# LPDDR4X_Power.net
KiCad netlist of a schematic drawn in Altium Designer
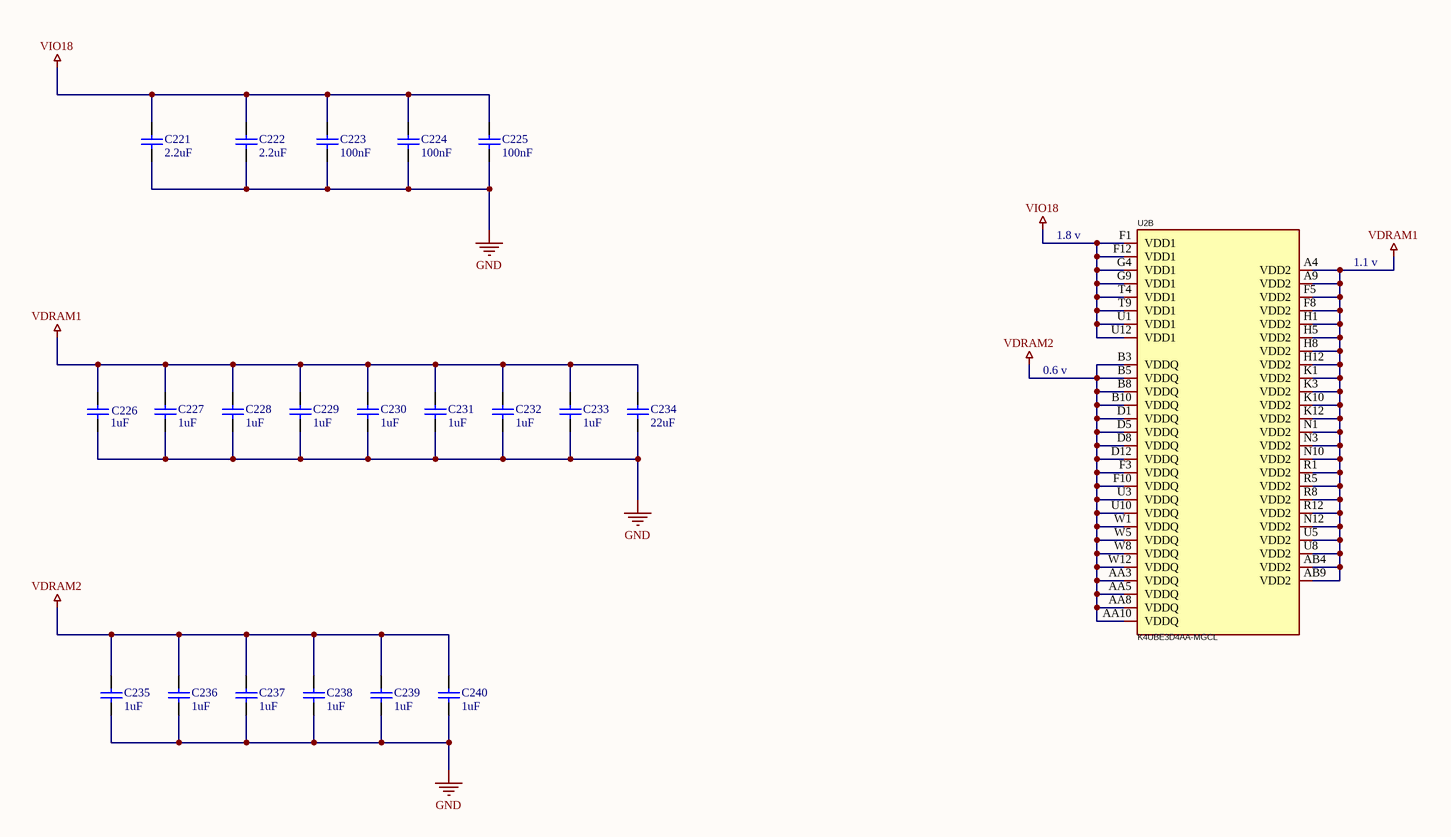
[diagram p0: LPDDR4X_Power.SchDoc]

(export (version "E")
  (design (tool "Eeschema 10.0.6"))
  (components
    (comp (ref "C221")
      (value "2.2uF")
      (footprint "C0805")
      (fields (field (name "Comment") "C0805"))
      (libsource (lib "kit") (part "C0805"))
    )
    (comp (ref "C222")
      (value "2.2uF")
      (footprint "C0805")
      (fields (field (name "Comment") "C0805"))
      (libsource (lib "kit") (part "C0805"))
    )
    (comp (ref "C223")
      (value "100nF")
      (footprint "C0603")
      (fields (field (name "Comment") "C0603"))
      (libsource (lib "kit") (part "C0603"))
    )
    (comp (ref "C224")
      (value "100nF")
      (footprint "C0603")
      (fields (field (name "Comment") "C0603"))
      (libsource (lib "kit") (part "C0603"))
    )
    (comp (ref "C225")
      (value "100nF")
      (footprint "C0603")
      (fields (field (name "Comment") "C0603"))
      (libsource (lib "kit") (part "C0603"))
    )
    (comp (ref "C226")
      (value "1uF")
      (footprint "C0805")
      (fields (field (name "Comment") "C0805"))
      (libsource (lib "kit") (part "C0805"))
    )
    (comp (ref "C227")
      (value "1uF")
      (footprint "C0805")
      (fields (field (name "Comment") "C0805"))
      (libsource (lib "kit") (part "C0805"))
    )
    (comp (ref "C228")
      (value "1uF")
      (footprint "C0805")
      (fields (field (name "Comment") "C0805"))
      (libsource (lib "kit") (part "C0805"))
    )
    (comp (ref "C229")
      (value "1uF")
      (footprint "C0805")
      (fields (field (name "Comment") "C0805"))
      (libsource (lib "kit") (part "C0805"))
    )
    (comp (ref "C230")
      (value "1uF")
      (footprint "C0805")
      (fields (field (name "Comment") "C0805"))
      (libsource (lib "kit") (part "C0805"))
    )
    (comp (ref "C231")
      (value "1uF")
      (footprint "C0805")
      (fields (field (name "Comment") "C0805"))
      (libsource (lib "kit") (part "C0805"))
    )
    (comp (ref "C232")
      (value "1uF")
      (footprint "C0805")
      (fields (field (name "Comment") "C0805"))
      (libsource (lib "kit") (part "C0805"))
    )
    (comp (ref "C233")
      (value "1uF")
      (footprint "C0805")
      (fields (field (name "Comment") "C0805"))
      (libsource (lib "kit") (part "C0805"))
    )
    (comp (ref "C234")
      (value "22uF")
      (footprint "C1210")
      (fields (field (name "Comment") "C1210"))
      (libsource (lib "kit") (part "C1210"))
    )
    (comp (ref "C235")
      (value "1uF")
      (footprint "C0805")
      (fields (field (name "Comment") "C0805"))
      (libsource (lib "kit") (part "C0805"))
    )
    (comp (ref "C236")
      (value "1uF")
      (footprint "C0805")
      (fields (field (name "Comment") "C0805"))
      (libsource (lib "kit") (part "C0805"))
    )
    (comp (ref "C237")
      (value "1uF")
      (footprint "C0805")
      (fields (field (name "Comment") "C0805"))
      (libsource (lib "kit") (part "C0805"))
    )
    (comp (ref "C238")
      (value "1uF")
      (footprint "C0805")
      (fields (field (name "Comment") "C0805"))
      (libsource (lib "kit") (part "C0805"))
    )
    (comp (ref "C239")
      (value "1uF")
      (footprint "C0805")
      (fields (field (name "Comment") "C0805"))
      (libsource (lib "kit") (part "C0805"))
    )
    (comp (ref "C240")
      (value "1uF")
      (footprint "C0805")
      (fields (field (name "Comment") "C0805"))
      (libsource (lib "kit") (part "C0805"))
    )
    (comp (ref "U2")
      (value "K4UBE3D4AA-MGCL")
      (footprint "K4F8E304HB-MGCJ")
      (fields (field (name "MANUFACTURER") "SAMSUNG(三星半导体)"))
      (libsource (lib "kit") (part "K4UBE3D4AA-MGCL"))
    )
  )
  (nets
    (net (code "1") (name "GND") (class "Default")
      (node (ref "C221") (pin "1") (pinfunction "1_1") (pintype "passive"))
      (node (ref "C222") (pin "1") (pinfunction "1_1") (pintype "passive"))
      (node (ref "C223") (pin "1") (pinfunction "1_1") (pintype "passive"))
      (node (ref "C224") (pin "1") (pinfunction "1_1") (pintype "passive"))
      (node (ref "C225") (pin "1") (pinfunction "1_1") (pintype "passive"))
      (node (ref "C226") (pin "1") (pinfunction "1_1") (pintype "passive"))
      (node (ref "C227") (pin "1") (pinfunction "1_1") (pintype "passive"))
      (node (ref "C228") (pin "1") (pinfunction "1_1") (pintype "passive"))
      (node (ref "C229") (pin "1") (pinfunction "1_1") (pintype "passive"))
      (node (ref "C230") (pin "1") (pinfunction "1_1") (pintype "passive"))
      (node (ref "C231") (pin "1") (pinfunction "1_1") (pintype "passive"))
      (node (ref "C232") (pin "1") (pinfunction "1_1") (pintype "passive"))
      (node (ref "C233") (pin "1") (pinfunction "1_1") (pintype "passive"))
      (node (ref "C234") (pin "1") (pinfunction "1_1") (pintype "passive"))
      (node (ref "C235") (pin "1") (pinfunction "1_1") (pintype "passive"))
      (node (ref "C236") (pin "1") (pinfunction "1_1") (pintype "passive"))
      (node (ref "C237") (pin "1") (pinfunction "1_1") (pintype "passive"))
      (node (ref "C238") (pin "1") (pinfunction "1_1") (pintype "passive"))
      (node (ref "C239") (pin "1") (pinfunction "1_1") (pintype "passive"))
      (node (ref "C240") (pin "1") (pinfunction "1_1") (pintype "passive"))
    )
    (net (code "2") (name "VDRAM1") (class "Default")
      (node (ref "C226") (pin "2") (pinfunction "2_2") (pintype "passive"))
      (node (ref "C227") (pin "2") (pinfunction "2_2") (pintype "passive"))
      (node (ref "C228") (pin "2") (pinfunction "2_2") (pintype "passive"))
      (node (ref "C229") (pin "2") (pinfunction "2_2") (pintype "passive"))
      (node (ref "C230") (pin "2") (pinfunction "2_2") (pintype "passive"))
      (node (ref "C231") (pin "2") (pinfunction "2_2") (pintype "passive"))
      (node (ref "C232") (pin "2") (pinfunction "2_2") (pintype "passive"))
      (node (ref "C233") (pin "2") (pinfunction "2_2") (pintype "passive"))
      (node (ref "C234") (pin "2") (pinfunction "2_2") (pintype "passive"))
      (node (ref "U2") (pin "A4") (pinfunction "VDD2_A4") (pintype "passive"))
      (node (ref "U2") (pin "A9") (pinfunction "VDD2_A9") (pintype "passive"))
      (node (ref "U2") (pin "AB4") (pinfunction "VDD2_AB4") (pintype "passive"))
      (node (ref "U2") (pin "AB9") (pinfunction "VDD2_AB9") (pintype "passive"))
      (node (ref "U2") (pin "F5") (pinfunction "VDD2_F5") (pintype "passive"))
      (node (ref "U2") (pin "F8") (pinfunction "VDD2_F8") (pintype "passive"))
      (node (ref "U2") (pin "H1") (pinfunction "VDD2_H1") (pintype "passive"))
      (node (ref "U2") (pin "H12") (pinfunction "VDD2_H12") (pintype "passive"))
      (node (ref "U2") (pin "H5") (pinfunction "VDD2_H5") (pintype "passive"))
      (node (ref "U2") (pin "H8") (pinfunction "VDD2_H8") (pintype "passive"))
      (node (ref "U2") (pin "K1") (pinfunction "VDD2_K1") (pintype "passive"))
      (node (ref "U2") (pin "K10") (pinfunction "VDD2_K10") (pintype "passive"))
      (node (ref "U2") (pin "K12") (pinfunction "VDD2_K12") (pintype "passive"))
      (node (ref "U2") (pin "K3") (pinfunction "VDD2_K3") (pintype "passive"))
      (node (ref "U2") (pin "N1") (pinfunction "VDD2_N1") (pintype "passive"))
      (node (ref "U2") (pin "N10") (pinfunction "VDD2_N10") (pintype "passive"))
      (node (ref "U2") (pin "N12") (pinfunction "VDD2_N12") (pintype "passive"))
      (node (ref "U2") (pin "N3") (pinfunction "VDD2_N3") (pintype "passive"))
      (node (ref "U2") (pin "R1") (pinfunction "VDD2_R1") (pintype "passive"))
      (node (ref "U2") (pin "R12") (pinfunction "VDD2_R12") (pintype "passive"))
      (node (ref "U2") (pin "R5") (pinfunction "VDD2_R5") (pintype "passive"))
      (node (ref "U2") (pin "R8") (pinfunction "VDD2_R8") (pintype "passive"))
      (node (ref "U2") (pin "U5") (pinfunction "VDD2_U5") (pintype "passive"))
      (node (ref "U2") (pin "U8") (pinfunction "VDD2_U8") (pintype "passive"))
    )
    (net (code "3") (name "VDRAM2") (class "Default")
      (node (ref "C235") (pin "2") (pinfunction "2_2") (pintype "passive"))
      (node (ref "C236") (pin "2") (pinfunction "2_2") (pintype "passive"))
      (node (ref "C237") (pin "2") (pinfunction "2_2") (pintype "passive"))
      (node (ref "C238") (pin "2") (pinfunction "2_2") (pintype "passive"))
      (node (ref "C239") (pin "2") (pinfunction "2_2") (pintype "passive"))
      (node (ref "C240") (pin "2") (pinfunction "2_2") (pintype "passive"))
      (node (ref "U2") (pin "AA10") (pinfunction "VDDQ_AA10") (pintype "passive"))
      (node (ref "U2") (pin "AA3") (pinfunction "VDDQ_AA3") (pintype "passive"))
      (node (ref "U2") (pin "AA5") (pinfunction "VDDQ_AA5") (pintype "passive"))
      (node (ref "U2") (pin "AA8") (pinfunction "VDDQ_AA8") (pintype "passive"))
      (node (ref "U2") (pin "B10") (pinfunction "VDDQ_B10") (pintype "passive"))
      (node (ref "U2") (pin "B3") (pinfunction "VDDQ_B3") (pintype "passive"))
      (node (ref "U2") (pin "B5") (pinfunction "VDDQ_B5") (pintype "passive"))
      (node (ref "U2") (pin "B8") (pinfunction "VDDQ_B8") (pintype "passive"))
      (node (ref "U2") (pin "D1") (pinfunction "VDDQ_D1") (pintype "passive"))
      (node (ref "U2") (pin "D12") (pinfunction "VDDQ_D12") (pintype "passive"))
      (node (ref "U2") (pin "D5") (pinfunction "VDDQ_D5") (pintype "passive"))
      (node (ref "U2") (pin "D8") (pinfunction "VDDQ_D8") (pintype "passive"))
      (node (ref "U2") (pin "F10") (pinfunction "VDDQ_F10") (pintype "passive"))
      (node (ref "U2") (pin "F3") (pinfunction "VDDQ_F3") (pintype "passive"))
      (node (ref "U2") (pin "U10") (pinfunction "VDDQ_U10") (pintype "passive"))
      (node (ref "U2") (pin "U3") (pinfunction "VDDQ_U3") (pintype "passive"))
      (node (ref "U2") (pin "W1") (pinfunction "VDDQ_W1") (pintype "passive"))
      (node (ref "U2") (pin "W12") (pinfunction "VDDQ_W12") (pintype "passive"))
      (node (ref "U2") (pin "W5") (pinfunction "VDDQ_W5") (pintype "passive"))
      (node (ref "U2") (pin "W8") (pinfunction "VDDQ_W8") (pintype "passive"))
    )
    (net (code "4") (name "VIO18") (class "Default")
      (node (ref "C221") (pin "2") (pinfunction "2_2") (pintype "passive"))
      (node (ref "C222") (pin "2") (pinfunction "2_2") (pintype "passive"))
      (node (ref "C223") (pin "2") (pinfunction "2_2") (pintype "passive"))
      (node (ref "C224") (pin "2") (pinfunction "2_2") (pintype "passive"))
      (node (ref "C225") (pin "2") (pinfunction "2_2") (pintype "passive"))
      (node (ref "U2") (pin "F1") (pinfunction "VDD1_F1") (pintype "passive"))
      (node (ref "U2") (pin "F12") (pinfunction "VDD1_F12") (pintype "passive"))
      (node (ref "U2") (pin "G4") (pinfunction "VDD1_G4") (pintype "passive"))
      (node (ref "U2") (pin "G9") (pinfunction "VDD1_G9") (pintype "passive"))
      (node (ref "U2") (pin "T4") (pinfunction "VDD1_T4") (pintype "passive"))
      (node (ref "U2") (pin "T9") (pinfunction "VDD1_T9") (pintype "passive"))
      (node (ref "U2") (pin "U1") (pinfunction "VDD1_U1") (pintype "passive"))
      (node (ref "U2") (pin "U12") (pinfunction "VDD1_U12") (pintype "passive"))
    )
  )
)
